# 2560_breakout.net
KiCad netlist of a schematic drawn in EAGLE
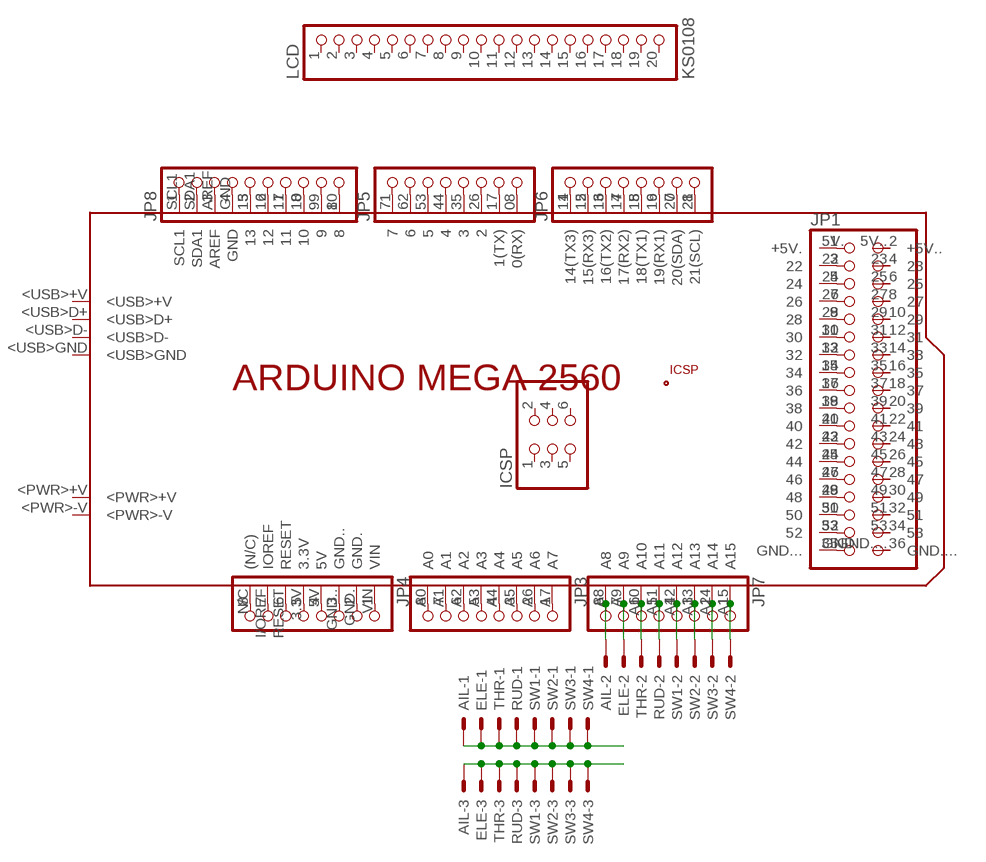
[diagram p0: schematic, sheet 1]

(export (version "E")
  (design (tool "Eeschema 10.0.6"))
  (components
    (comp (ref "AIL")
      (value "JST-XH-03-PIN-LONG-PAD")
      (footprint "eagle-import:JST-XH-03-PACKAGE-LONG-PAD")
      (libsource (lib "eagle-import") (part "JST-XH-03-PIN-LONG-PAD"))
    )
    (comp (ref "ELE")
      (value "JST-XH-03-PIN-LONG-PAD")
      (footprint "eagle-import:JST-XH-03-PACKAGE-LONG-PAD")
      (libsource (lib "eagle-import") (part "JST-XH-03-PIN-LONG-PAD"))
    )
    (comp (ref "ICSP")
      (value "PINHD-2X3")
      (footprint "eagle-import:2X03")
      (libsource (lib "eagle-import") (part "PINHD-2X3"))
    )
    (comp (ref "JP1")
      (value "PINHD-2X18")
      (footprint "eagle-import:2X18")
      (libsource (lib "eagle-import") (part "PINHD-2X18"))
    )
    (comp (ref "JP3")
      (value "PINHD-1X8")
      (footprint "eagle-import:1X08")
      (libsource (lib "eagle-import") (part "PINHD-1X8"))
    )
    (comp (ref "JP4")
      (value "PINHD-1X8")
      (footprint "eagle-import:1X08")
      (libsource (lib "eagle-import") (part "PINHD-1X8"))
    )
    (comp (ref "JP5")
      (value "PINHD-1X8")
      (footprint "eagle-import:1X08")
      (libsource (lib "eagle-import") (part "PINHD-1X8"))
    )
    (comp (ref "JP6")
      (value "PINHD-1X8")
      (footprint "eagle-import:1X08")
      (libsource (lib "eagle-import") (part "PINHD-1X8"))
    )
    (comp (ref "JP7")
      (value "PINHD-1X8")
      (footprint "eagle-import:1X08")
      (libsource (lib "eagle-import") (part "PINHD-1X8"))
    )
    (comp (ref "JP8")
      (value "PINHD-1X10")
      (footprint "eagle-import:1X10")
      (libsource (lib "eagle-import") (part "PINHD-1X10"))
    )
    (comp (ref "LCD")
      (value "KS0108")
      (footprint "eagle-import:1X20")
      (libsource (lib "eagle-import") (part "PINHD-1X20"))
    )
    (comp (ref "PCB1")
      (value "ARDUINO_MEGA2560")
      (footprint "eagle-import:ARDUINO_MEGA2560")
      (libsource (lib "eagle-import") (part "ARDUINO_MEGA2560"))
    )
    (comp (ref "RUD")
      (value "JST-XH-03-PIN-LONG-PAD")
      (footprint "eagle-import:JST-XH-03-PACKAGE-LONG-PAD")
      (libsource (lib "eagle-import") (part "JST-XH-03-PIN-LONG-PAD"))
    )
    (comp (ref "SW1")
      (value "JST-XH-03-PIN-LONG-PAD")
      (footprint "eagle-import:JST-XH-03-PACKAGE-LONG-PAD")
      (libsource (lib "eagle-import") (part "JST-XH-03-PIN-LONG-PAD"))
    )
    (comp (ref "SW2")
      (value "JST-XH-03-PIN-LONG-PAD")
      (footprint "eagle-import:JST-XH-03-PACKAGE-LONG-PAD")
      (libsource (lib "eagle-import") (part "JST-XH-03-PIN-LONG-PAD"))
    )
    (comp (ref "SW3")
      (value "JST-XH-03-PIN-LONG-PAD")
      (footprint "eagle-import:JST-XH-03-PACKAGE-LONG-PAD")
      (libsource (lib "eagle-import") (part "JST-XH-03-PIN-LONG-PAD"))
    )
    (comp (ref "SW4")
      (value "JST-XH-03-PIN-LONG-PAD")
      (footprint "eagle-import:JST-XH-03-PACKAGE-LONG-PAD")
      (libsource (lib "eagle-import") (part "JST-XH-03-PIN-LONG-PAD"))
    )
    (comp (ref "THR")
      (value "JST-XH-03-PIN-LONG-PAD")
      (footprint "eagle-import:JST-XH-03-PACKAGE-LONG-PAD")
      (libsource (lib "eagle-import") (part "JST-XH-03-PIN-LONG-PAD"))
    )
  )
  (nets
    (net (code "1") (name "Net-(AILA-S)") (class "Default")
      (node (ref "AIL") (pin "1") (pinfunction "S_1") (pintype "passive"))
      (node (ref "ELE") (pin "1") (pinfunction "S_1") (pintype "passive"))
      (node (ref "RUD") (pin "1") (pinfunction "S_1") (pintype "passive"))
      (node (ref "SW1") (pin "1") (pinfunction "S_1") (pintype "passive"))
      (node (ref "SW2") (pin "1") (pinfunction "S_1") (pintype "passive"))
      (node (ref "SW3") (pin "1") (pinfunction "S_1") (pintype "passive"))
      (node (ref "SW4") (pin "1") (pinfunction "S_1") (pintype "passive"))
      (node (ref "THR") (pin "1") (pinfunction "S_1") (pintype "passive"))
    )
    (net (code "2") (name "Net-(AILB-S)") (class "Default")
      (node (ref "AIL") (pin "2") (pinfunction "S_2") (pintype "passive"))
      (node (ref "JP7") (pin "8") (pinfunction "8_8") (pintype "passive"))
      (node (ref "PCB1") (pin "A8") (pinfunction "A8_A8") (pintype "bidirectional"))
    )
    (net (code "3") (name "Net-(AILC-S)") (class "Default")
      (node (ref "AIL") (pin "3") (pinfunction "S_3") (pintype "passive"))
      (node (ref "ELE") (pin "3") (pinfunction "S_3") (pintype "passive"))
      (node (ref "RUD") (pin "3") (pinfunction "S_3") (pintype "passive"))
      (node (ref "SW1") (pin "3") (pinfunction "S_3") (pintype "passive"))
      (node (ref "SW2") (pin "3") (pinfunction "S_3") (pintype "passive"))
      (node (ref "SW3") (pin "3") (pinfunction "S_3") (pintype "passive"))
      (node (ref "SW4") (pin "3") (pinfunction "S_3") (pintype "passive"))
      (node (ref "THR") (pin "3") (pinfunction "S_3") (pintype "passive"))
    )
    (net (code "4") (name "Net-(ELEB-S)") (class "Default")
      (node (ref "ELE") (pin "2") (pinfunction "S_2") (pintype "passive"))
      (node (ref "JP7") (pin "7") (pinfunction "7_7") (pintype "passive"))
      (node (ref "PCB1") (pin "A9") (pinfunction "A9_A9") (pintype "bidirectional"))
    )
    (net (code "5") (name "Net-(JP1-Pad3)") (class "Default")
      (node (ref "JP1") (pin "3") (pinfunction "3_3") (pintype "passive"))
      (node (ref "PCB1") (pin "22") (pinfunction "22_22") (pintype "bidirectional"))
    )
    (net (code "6") (name "Net-(JP1-Pad5)") (class "Default")
      (node (ref "JP1") (pin "5") (pinfunction "5_5") (pintype "passive"))
      (node (ref "PCB1") (pin "24") (pinfunction "24_24") (pintype "bidirectional"))
    )
    (net (code "7") (name "Net-(JP1-Pad7)") (class "Default")
      (node (ref "JP1") (pin "7") (pinfunction "7_7") (pintype "passive"))
      (node (ref "PCB1") (pin "26") (pinfunction "26_26") (pintype "bidirectional"))
    )
    (net (code "8") (name "Net-(JP1-Pad9)") (class "Default")
      (node (ref "JP1") (pin "9") (pinfunction "9_9") (pintype "passive"))
      (node (ref "PCB1") (pin "28") (pinfunction "28_28") (pintype "bidirectional"))
    )
    (net (code "9") (name "Net-(JP1-Pad11)") (class "Default")
      (node (ref "JP1") (pin "11") (pinfunction "11_11") (pintype "passive"))
      (node (ref "PCB1") (pin "30") (pinfunction "30_30") (pintype "bidirectional"))
    )
    (net (code "10") (name "Net-(JP1-Pad13)") (class "Default")
      (node (ref "JP1") (pin "13") (pinfunction "13_13") (pintype "passive"))
      (node (ref "PCB1") (pin "32") (pinfunction "32_32") (pintype "bidirectional"))
    )
    (net (code "11") (name "Net-(JP1-Pad15)") (class "Default")
      (node (ref "JP1") (pin "15") (pinfunction "15_15") (pintype "passive"))
      (node (ref "PCB1") (pin "34") (pinfunction "34_34") (pintype "bidirectional"))
    )
    (net (code "12") (name "Net-(JP1-Pad17)") (class "Default")
      (node (ref "JP1") (pin "17") (pinfunction "17_17") (pintype "passive"))
      (node (ref "PCB1") (pin "36") (pinfunction "36_36") (pintype "bidirectional"))
    )
    (net (code "13") (name "Net-(JP1-Pad19)") (class "Default")
      (node (ref "JP1") (pin "19") (pinfunction "19_19") (pintype "passive"))
      (node (ref "PCB1") (pin "38") (pinfunction "38_38") (pintype "bidirectional"))
    )
    (net (code "14") (name "Net-(JP1-Pad21)") (class "Default")
      (node (ref "JP1") (pin "21") (pinfunction "21_21") (pintype "passive"))
      (node (ref "PCB1") (pin "40") (pinfunction "40_40") (pintype "bidirectional"))
    )
    (net (code "15") (name "Net-(JP1-Pad23)") (class "Default")
      (node (ref "JP1") (pin "23") (pinfunction "23_23") (pintype "passive"))
      (node (ref "PCB1") (pin "42") (pinfunction "42_42") (pintype "bidirectional"))
    )
    (net (code "16") (name "Net-(JP1-Pad25)") (class "Default")
      (node (ref "JP1") (pin "25") (pinfunction "25_25") (pintype "passive"))
      (node (ref "PCB1") (pin "44") (pinfunction "44_44") (pintype "bidirectional"))
    )
    (net (code "17") (name "Net-(JP1-Pad27)") (class "Default")
      (node (ref "JP1") (pin "27") (pinfunction "27_27") (pintype "passive"))
      (node (ref "PCB1") (pin "46") (pinfunction "46_46") (pintype "bidirectional"))
    )
    (net (code "18") (name "Net-(JP1-Pad29)") (class "Default")
      (node (ref "JP1") (pin "29") (pinfunction "29_29") (pintype "passive"))
      (node (ref "PCB1") (pin "48") (pinfunction "48_48") (pintype "bidirectional"))
    )
    (net (code "19") (name "Net-(JP1-Pad31)") (class "Default")
      (node (ref "JP1") (pin "31") (pinfunction "31_31") (pintype "passive"))
      (node (ref "PCB1") (pin "50") (pinfunction "50_50") (pintype "bidirectional"))
    )
    (net (code "20") (name "Net-(JP1-Pad33)") (class "Default")
      (node (ref "JP1") (pin "33") (pinfunction "33_33") (pintype "passive"))
      (node (ref "PCB1") (pin "52") (pinfunction "52_52") (pintype "bidirectional"))
    )
    (net (code "21") (name "Net-(JP1-Pad35)") (class "Default")
      (node (ref "JP1") (pin "35") (pinfunction "35_35") (pintype "passive"))
      (node (ref "PCB1") (pin "GND...") (pinfunction "GND..._GND...") (pintype "bidirectional"))
    )
    (net (code "22") (name "Net-(JP3-Pad1)") (class "Default")
      (node (ref "JP3") (pin "1") (pinfunction "1_1") (pintype "passive"))
      (node (ref "PCB1") (pin "A7") (pinfunction "A7_A7") (pintype "bidirectional"))
    )
    (net (code "23") (name "Net-(JP3-Pad2)") (class "Default")
      (node (ref "JP3") (pin "2") (pinfunction "2_2") (pintype "passive"))
      (node (ref "PCB1") (pin "A6") (pinfunction "A6_A6") (pintype "bidirectional"))
    )
    (net (code "24") (name "Net-(JP3-Pad3)") (class "Default")
      (node (ref "JP3") (pin "3") (pinfunction "3_3") (pintype "passive"))
      (node (ref "PCB1") (pin "A5") (pinfunction "A5_A5") (pintype "bidirectional"))
    )
    (net (code "25") (name "Net-(JP3-Pad4)") (class "Default")
      (node (ref "JP3") (pin "4") (pinfunction "4_4") (pintype "passive"))
      (node (ref "PCB1") (pin "A4") (pinfunction "A4_A4") (pintype "bidirectional"))
    )
    (net (code "26") (name "Net-(JP3-Pad5)") (class "Default")
      (node (ref "JP3") (pin "5") (pinfunction "5_5") (pintype "passive"))
      (node (ref "PCB1") (pin "A3") (pinfunction "A3_A3") (pintype "bidirectional"))
    )
    (net (code "27") (name "Net-(JP3-Pad6)") (class "Default")
      (node (ref "JP3") (pin "6") (pinfunction "6_6") (pintype "passive"))
      (node (ref "PCB1") (pin "A2") (pinfunction "A2_A2") (pintype "bidirectional"))
    )
    (net (code "28") (name "Net-(JP3-Pad7)") (class "Default")
      (node (ref "JP3") (pin "7") (pinfunction "7_7") (pintype "passive"))
      (node (ref "PCB1") (pin "A1") (pinfunction "A1_A1") (pintype "bidirectional"))
    )
    (net (code "29") (name "Net-(JP3-Pad8)") (class "Default")
      (node (ref "JP3") (pin "8") (pinfunction "8_8") (pintype "passive"))
      (node (ref "PCB1") (pin "A0") (pinfunction "A0_A0") (pintype "bidirectional"))
    )
    (net (code "30") (name "Net-(JP4-Pad1)") (class "Default")
      (node (ref "JP4") (pin "1") (pinfunction "1_1") (pintype "passive"))
      (node (ref "PCB1") (pin "VIN") (pinfunction "VIN_VIN") (pintype "bidirectional"))
    )
    (net (code "31") (name "Net-(JP4-Pad2)") (class "Default")
      (node (ref "JP4") (pin "2") (pinfunction "2_2") (pintype "passive"))
      (node (ref "PCB1") (pin "GND.") (pinfunction "GND._GND.") (pintype "bidirectional"))
    )
    (net (code "32") (name "Net-(JP4-Pad3)") (class "Default")
      (node (ref "JP4") (pin "3") (pinfunction "3_3") (pintype "passive"))
      (node (ref "PCB1") (pin "GND..") (pinfunction "GND.._GND..") (pintype "bidirectional"))
    )
    (net (code "33") (name "Net-(JP4-Pad4)") (class "Default")
      (node (ref "JP4") (pin "4") (pinfunction "4_4") (pintype "passive"))
      (node (ref "PCB1") (pin "5V") (pinfunction "5V_5V") (pintype "bidirectional"))
    )
    (net (code "34") (name "Net-(JP4-Pad5)") (class "Default")
      (node (ref "JP4") (pin "5") (pinfunction "5_5") (pintype "passive"))
      (node (ref "PCB1") (pin "3.3V") (pinfunction "3.3V_3.3V") (pintype "bidirectional"))
    )
    (net (code "35") (name "Net-(JP4-Pad6)") (class "Default")
      (node (ref "JP4") (pin "6") (pinfunction "6_6") (pintype "passive"))
      (node (ref "PCB1") (pin "RESET") (pinfunction "RESET_RESET") (pintype "bidirectional"))
    )
    (net (code "36") (name "Net-(JP5-Pad1)") (class "Default")
      (node (ref "JP5") (pin "1") (pinfunction "1_1") (pintype "passive"))
      (node (ref "PCB1") (pin "7") (pinfunction "7_7") (pintype "bidirectional"))
    )
    (net (code "37") (name "Net-(JP5-Pad2)") (class "Default")
      (node (ref "JP5") (pin "2") (pinfunction "2_2") (pintype "passive"))
      (node (ref "PCB1") (pin "6") (pinfunction "6_6") (pintype "bidirectional"))
    )
    (net (code "38") (name "Net-(JP5-Pad3)") (class "Default")
      (node (ref "JP5") (pin "3") (pinfunction "3_3") (pintype "passive"))
      (node (ref "PCB1") (pin "5") (pinfunction "5_5") (pintype "bidirectional"))
    )
    (net (code "39") (name "Net-(JP5-Pad4)") (class "Default")
      (node (ref "JP5") (pin "4") (pinfunction "4_4") (pintype "passive"))
      (node (ref "PCB1") (pin "4") (pinfunction "4_4") (pintype "bidirectional"))
    )
    (net (code "40") (name "Net-(JP5-Pad5)") (class "Default")
      (node (ref "JP5") (pin "5") (pinfunction "5_5") (pintype "passive"))
      (node (ref "PCB1") (pin "3") (pinfunction "3_3") (pintype "bidirectional"))
    )
    (net (code "41") (name "Net-(JP5-Pad6)") (class "Default")
      (node (ref "JP5") (pin "6") (pinfunction "6_6") (pintype "passive"))
      (node (ref "PCB1") (pin "2") (pinfunction "2_2") (pintype "bidirectional"))
    )
    (net (code "42") (name "Net-(JP8-Pad1)") (class "Default")
      (node (ref "JP8") (pin "1") (pinfunction "1_1") (pintype "passive"))
      (node (ref "PCB1") (pin "SCL1") (pinfunction "SCL1_SCL1") (pintype "bidirectional"))
    )
    (net (code "43") (name "Net-(JP8-Pad2)") (class "Default")
      (node (ref "JP8") (pin "2") (pinfunction "2_2") (pintype "passive"))
      (node (ref "PCB1") (pin "SDA1") (pinfunction "SDA1_SDA1") (pintype "bidirectional"))
    )
    (net (code "44") (name "Net-(JP8-Pad3)") (class "Default")
      (node (ref "JP8") (pin "3") (pinfunction "3_3") (pintype "passive"))
      (node (ref "PCB1") (pin "AREF") (pinfunction "AREF_AREF") (pintype "bidirectional"))
    )
    (net (code "45") (name "Net-(JP8-Pad4)") (class "Default")
      (node (ref "JP8") (pin "4") (pinfunction "4_4") (pintype "passive"))
      (node (ref "PCB1") (pin "GND") (pinfunction "GND_GND") (pintype "bidirectional"))
    )
    (net (code "46") (name "Net-(JP8-Pad5)") (class "Default")
      (node (ref "JP8") (pin "5") (pinfunction "5_5") (pintype "passive"))
      (node (ref "PCB1") (pin "13") (pinfunction "13_13") (pintype "bidirectional"))
    )
    (net (code "47") (name "Net-(JP8-Pad6)") (class "Default")
      (node (ref "JP8") (pin "6") (pinfunction "6_6") (pintype "passive"))
      (node (ref "PCB1") (pin "12") (pinfunction "12_12") (pintype "bidirectional"))
    )
    (net (code "48") (name "Net-(JP8-Pad7)") (class "Default")
      (node (ref "JP8") (pin "7") (pinfunction "7_7") (pintype "passive"))
      (node (ref "PCB1") (pin "11") (pinfunction "11_11") (pintype "bidirectional"))
    )
    (net (code "49") (name "Net-(JP8-Pad8)") (class "Default")
      (node (ref "JP8") (pin "8") (pinfunction "8_8") (pintype "passive"))
      (node (ref "PCB1") (pin "10") (pinfunction "10_10") (pintype "bidirectional"))
    )
    (net (code "50") (name "Net-(JP8-Pad9)") (class "Default")
      (node (ref "JP8") (pin "9") (pinfunction "9_9") (pintype "passive"))
      (node (ref "PCB1") (pin "9") (pinfunction "9_9") (pintype "bidirectional"))
    )
    (net (code "51") (name "Net-(JP8-Pad10)") (class "Default")
      (node (ref "JP8") (pin "10") (pinfunction "10_10") (pintype "passive"))
      (node (ref "PCB1") (pin "8") (pinfunction "8_8") (pintype "bidirectional"))
    )
    (net (code "52") (name "Net-(PCB1-(N{slash}C))") (class "Default")
      (node (ref "JP4") (pin "8") (pinfunction "8_8") (pintype "passive"))
      (node (ref "PCB1") (pin "N/C") (pinfunction "(N/C)_N/C") (pintype "bidirectional"))
    )
    (net (code "53") (name "Net-(PCB1-+5V.)") (class "Default")
      (node (ref "JP1") (pin "1") (pinfunction "1_1") (pintype "passive"))
      (node (ref "PCB1") (pin "5V.") (pinfunction "+5V._5V.") (pintype "bidirectional"))
    )
    (net (code "54") (name "Net-(PCB1-0(RX))") (class "Default")
      (node (ref "JP5") (pin "8") (pinfunction "8_8") (pintype "passive"))
      (node (ref "PCB1") (pin "0") (pinfunction "0(RX)_0") (pintype "bidirectional"))
    )
    (net (code "55") (name "Net-(PCB1-1(TX))") (class "Default")
      (node (ref "JP5") (pin "7") (pinfunction "7_7") (pintype "passive"))
      (node (ref "PCB1") (pin "1") (pinfunction "1(TX)_1") (pintype "bidirectional"))
    )
    (net (code "56") (name "Net-(PCB1-14(TX3))") (class "Default")
      (node (ref "JP6") (pin "1") (pinfunction "1_1") (pintype "passive"))
      (node (ref "PCB1") (pin "14") (pinfunction "14(TX3)_14") (pintype "bidirectional"))
    )
    (net (code "57") (name "Net-(PCB1-15(RX3))") (class "Default")
      (node (ref "JP6") (pin "2") (pinfunction "2_2") (pintype "passive"))
      (node (ref "PCB1") (pin "15") (pinfunction "15(RX3)_15") (pintype "bidirectional"))
    )
    (net (code "58") (name "Net-(PCB1-16(TX2))") (class "Default")
      (node (ref "JP6") (pin "3") (pinfunction "3_3") (pintype "passive"))
      (node (ref "PCB1") (pin "16") (pinfunction "16(TX2)_16") (pintype "bidirectional"))
    )
    (net (code "59") (name "Net-(PCB1-17(RX2))") (class "Default")
      (node (ref "JP6") (pin "4") (pinfunction "4_4") (pintype "passive"))
      (node (ref "PCB1") (pin "17") (pinfunction "17(RX2)_17") (pintype "bidirectional"))
    )
    (net (code "60") (name "Net-(PCB1-18(TX1))") (class "Default")
      (node (ref "JP6") (pin "5") (pinfunction "5_5") (pintype "passive"))
      (node (ref "PCB1") (pin "18") (pinfunction "18(TX1)_18") (pintype "bidirectional"))
    )
    (net (code "61") (name "Net-(PCB1-19(RX1))") (class "Default")
      (node (ref "JP6") (pin "6") (pinfunction "6_6") (pintype "passive"))
      (node (ref "PCB1") (pin "19") (pinfunction "19(RX1)_19") (pintype "bidirectional"))
    )
    (net (code "62") (name "Net-(PCB1-20(SDA))") (class "Default")
      (node (ref "JP6") (pin "7") (pinfunction "7_7") (pintype "passive"))
      (node (ref "PCB1") (pin "20") (pinfunction "20(SDA)_20") (pintype "bidirectional"))
    )
    (net (code "63") (name "Net-(PCB1-21(SCL))") (class "Default")
      (node (ref "JP6") (pin "8") (pinfunction "8_8") (pintype "passive"))
      (node (ref "PCB1") (pin "21") (pinfunction "21(SCL)_21") (pintype "bidirectional"))
    )
    (net (code "64") (name "Net-(PCB1-IOREF)") (class "Default")
      (node (ref "JP4") (pin "7") (pinfunction "7_7") (pintype "passive"))
      (node (ref "PCB1") (pin "I/OREF") (pinfunction "IOREF_I/OREF") (pintype "bidirectional"))
    )
    (net (code "65") (name "Net-(RUDB-S)") (class "Default")
      (node (ref "JP7") (pin "5") (pinfunction "5_5") (pintype "passive"))
      (node (ref "PCB1") (pin "A11") (pinfunction "A11_A11") (pintype "bidirectional"))
      (node (ref "RUD") (pin "2") (pinfunction "S_2") (pintype "passive"))
    )
    (net (code "66") (name "Net-(SW1B-S)") (class "Default")
      (node (ref "JP7") (pin "4") (pinfunction "4_4") (pintype "passive"))
      (node (ref "PCB1") (pin "A12") (pinfunction "A12_A12") (pintype "bidirectional"))
      (node (ref "SW1") (pin "2") (pinfunction "S_2") (pintype "passive"))
    )
    (net (code "67") (name "Net-(SW2B-S)") (class "Default")
      (node (ref "JP7") (pin "3") (pinfunction "3_3") (pintype "passive"))
      (node (ref "PCB1") (pin "A13") (pinfunction "A13_A13") (pintype "bidirectional"))
      (node (ref "SW2") (pin "2") (pinfunction "S_2") (pintype "passive"))
    )
    (net (code "68") (name "Net-(SW3B-S)") (class "Default")
      (node (ref "JP7") (pin "2") (pinfunction "2_2") (pintype "passive"))
      (node (ref "PCB1") (pin "A14") (pinfunction "A14_A14") (pintype "bidirectional"))
      (node (ref "SW3") (pin "2") (pinfunction "S_2") (pintype "passive"))
    )
    (net (code "69") (name "Net-(SW4B-S)") (class "Default")
      (node (ref "JP7") (pin "1") (pinfunction "1_1") (pintype "passive"))
      (node (ref "PCB1") (pin "A15") (pinfunction "A15_A15") (pintype "bidirectional"))
      (node (ref "SW4") (pin "2") (pinfunction "S_2") (pintype "passive"))
    )
    (net (code "70") (name "Net-(THRB-S)") (class "Default")
      (node (ref "JP7") (pin "6") (pinfunction "6_6") (pintype "passive"))
      (node (ref "PCB1") (pin "A10") (pinfunction "A10_A10") (pintype "bidirectional"))
      (node (ref "THR") (pin "2") (pinfunction "S_2") (pintype "passive"))
    )
    (net (code "71") (name "unconnected-(ICSP-Pad1)") (class "Default")
      (node (ref "ICSP") (pin "1") (pinfunction "1_1") (pintype "passive"))
    )
    (net (code "72") (name "unconnected-(ICSP-Pad2)") (class "Default")
      (node (ref "ICSP") (pin "2") (pinfunction "2_2") (pintype "passive"))
    )
    (net (code "73") (name "unconnected-(ICSP-Pad3)") (class "Default")
      (node (ref "ICSP") (pin "3") (pinfunction "3_3") (pintype "passive"))
    )
    (net (code "74") (name "unconnected-(ICSP-Pad4)") (class "Default")
      (node (ref "ICSP") (pin "4") (pinfunction "4_4") (pintype "passive"))
    )
    (net (code "75") (name "unconnected-(ICSP-Pad5)") (class "Default")
      (node (ref "ICSP") (pin "5") (pinfunction "5_5") (pintype "passive"))
    )
    (net (code "76") (name "unconnected-(ICSP-Pad6)") (class "Default")
      (node (ref "ICSP") (pin "6") (pinfunction "6_6") (pintype "passive"))
    )
    (net (code "77") (name "unconnected-(JP1-Pad2)") (class "Default")
      (node (ref "JP1") (pin "2") (pinfunction "2_2") (pintype "passive"))
    )
    (net (code "78") (name "unconnected-(JP1-Pad4)") (class "Default")
      (node (ref "JP1") (pin "4") (pinfunction "4_4") (pintype "passive"))
    )
    (net (code "79") (name "unconnected-(JP1-Pad6)") (class "Default")
      (node (ref "JP1") (pin "6") (pinfunction "6_6") (pintype "passive"))
    )
    (net (code "80") (name "unconnected-(JP1-Pad8)") (class "Default")
      (node (ref "JP1") (pin "8") (pinfunction "8_8") (pintype "passive"))
    )
    (net (code "81") (name "unconnected-(JP1-Pad10)") (class "Default")
      (node (ref "JP1") (pin "10") (pinfunction "10_10") (pintype "passive"))
    )
    (net (code "82") (name "unconnected-(JP1-Pad12)") (class "Default")
      (node (ref "JP1") (pin "12") (pinfunction "12_12") (pintype "passive"))
    )
    (net (code "83") (name "unconnected-(JP1-Pad14)") (class "Default")
      (node (ref "JP1") (pin "14") (pinfunction "14_14") (pintype "passive"))
    )
    (net (code "84") (name "unconnected-(JP1-Pad16)") (class "Default")
      (node (ref "JP1") (pin "16") (pinfunction "16_16") (pintype "passive"))
    )
    (net (code "85") (name "unconnected-(JP1-Pad18)") (class "Default")
      (node (ref "JP1") (pin "18") (pinfunction "18_18") (pintype "passive"))
    )
    (net (code "86") (name "unconnected-(JP1-Pad20)") (class "Default")
      (node (ref "JP1") (pin "20") (pinfunction "20_20") (pintype "passive"))
    )
    (net (code "87") (name "unconnected-(JP1-Pad22)") (class "Default")
      (node (ref "JP1") (pin "22") (pinfunction "22_22") (pintype "passive"))
    )
    (net (code "88") (name "unconnected-(JP1-Pad24)") (class "Default")
      (node (ref "JP1") (pin "24") (pinfunction "24_24") (pintype "passive"))
    )
    (net (code "89") (name "unconnected-(JP1-Pad26)") (class "Default")
      (node (ref "JP1") (pin "26") (pinfunction "26_26") (pintype "passive"))
    )
    (net (code "90") (name "unconnected-(JP1-Pad28)") (class "Default")
      (node (ref "JP1") (pin "28") (pinfunction "28_28") (pintype "passive"))
    )
    (net (code "91") (name "unconnected-(JP1-Pad30)") (class "Default")
      (node (ref "JP1") (pin "30") (pinfunction "30_30") (pintype "passive"))
    )
    (net (code "92") (name "unconnected-(JP1-Pad32)") (class "Default")
      (node (ref "JP1") (pin "32") (pinfunction "32_32") (pintype "passive"))
    )
    (net (code "93") (name "unconnected-(JP1-Pad34)") (class "Default")
      (node (ref "JP1") (pin "34") (pinfunction "34_34") (pintype "passive"))
    )
    (net (code "94") (name "unconnected-(JP1-Pad36)") (class "Default")
      (node (ref "JP1") (pin "36") (pinfunction "36_36") (pintype "passive"))
    )
    (net (code "95") (name "unconnected-(LCD-Pad1)") (class "Default")
      (node (ref "LCD") (pin "1") (pinfunction "1_1") (pintype "passive"))
    )
    (net (code "96") (name "unconnected-(LCD-Pad2)") (class "Default")
      (node (ref "LCD") (pin "2") (pinfunction "2_2") (pintype "passive"))
    )
    (net (code "97") (name "unconnected-(LCD-Pad3)") (class "Default")
      (node (ref "LCD") (pin "3") (pinfunction "3_3") (pintype "passive"))
    )
    (net (code "98") (name "unconnected-(LCD-Pad4)") (class "Default")
      (node (ref "LCD") (pin "4") (pinfunction "4_4") (pintype "passive"))
    )
    (net (code "99") (name "unconnected-(LCD-Pad5)") (class "Default")
      (node (ref "LCD") (pin "5") (pinfunction "5_5") (pintype "passive"))
    )
    (net (code "100") (name "unconnected-(LCD-Pad6)") (class "Default")
      (node (ref "LCD") (pin "6") (pinfunction "6_6") (pintype "passive"))
    )
    (net (code "101") (name "unconnected-(LCD-Pad7)") (class "Default")
      (node (ref "LCD") (pin "7") (pinfunction "7_7") (pintype "passive"))
    )
    (net (code "102") (name "unconnected-(LCD-Pad8)") (class "Default")
      (node (ref "LCD") (pin "8") (pinfunction "8_8") (pintype "passive"))
    )
    (net (code "103") (name "unconnected-(LCD-Pad9)") (class "Default")
      (node (ref "LCD") (pin "9") (pinfunction "9_9") (pintype "passive"))
    )
    (net (code "104") (name "unconnected-(LCD-Pad10)") (class "Default")
      (node (ref "LCD") (pin "10") (pinfunction "10_10") (pintype "passive"))
    )
    (net (code "105") (name "unconnected-(LCD-Pad11)") (class "Default")
      (node (ref "LCD") (pin "11") (pinfunction "11_11") (pintype "passive"))
    )
    (net (code "106") (name "unconnected-(LCD-Pad12)") (class "Default")
      (node (ref "LCD") (pin "12") (pinfunction "12_12") (pintype "passive"))
    )
    (net (code "107") (name "unconnected-(LCD-Pad13)") (class "Default")
      (node (ref "LCD") (pin "13") (pinfunction "13_13") (pintype "passive"))
    )
    (net (code "108") (name "unconnected-(LCD-Pad14)") (class "Default")
      (node (ref "LCD") (pin "14") (pinfunction "14_14") (pintype "passive"))
    )
    (net (code "109") (name "unconnected-(LCD-Pad15)") (class "Default")
      (node (ref "LCD") (pin "15") (pinfunction "15_15") (pintype "passive"))
    )
    (net (code "110") (name "unconnected-(LCD-Pad16)") (class "Default")
      (node (ref "LCD") (pin "16") (pinfunction "16_16") (pintype "passive"))
    )
    (net (code "111") (name "unconnected-(LCD-Pad17)") (class "Default")
      (node (ref "LCD") (pin "17") (pinfunction "17_17") (pintype "passive"))
    )
    (net (code "112") (name "unconnected-(LCD-Pad18)") (class "Default")
      (node (ref "LCD") (pin "18") (pinfunction "18_18") (pintype "passive"))
    )
    (net (code "113") (name "unconnected-(LCD-Pad19)") (class "Default")
      (node (ref "LCD") (pin "19") (pinfunction "19_19") (pintype "passive"))
    )
    (net (code "114") (name "unconnected-(LCD-Pad20)") (class "Default")
      (node (ref "LCD") (pin "20") (pinfunction "20_20") (pintype "passive"))
    )
    (net (code "115") (name "unconnected-(PCB1-+5V..-Pad5V..)") (class "Default")
      (node (ref "PCB1") (pin "5V..") (pinfunction "+5V.._5V..") (pintype "bidirectional"))
    )
    (net (code "116") (name "unconnected-(PCB1-Pad+5V_)") (class "Default")
      (node (ref "PCB1") (pin "+5V_") (pinfunction "+5V__+5V_") (pintype "bidirectional"))
    )
    (net (code "117") (name "unconnected-(PCB1-Pad23)") (class "Default")
      (node (ref "PCB1") (pin "23") (pinfunction "23_23") (pintype "bidirectional"))
    )
    (net (code "118") (name "unconnected-(PCB1-Pad25)") (class "Default")
      (node (ref "PCB1") (pin "25") (pinfunction "25_25") (pintype "bidirectional"))
    )
    (net (code "119") (name "unconnected-(PCB1-Pad27)") (class "Default")
      (node (ref "PCB1") (pin "27") (pinfunction "27_27") (pintype "bidirectional"))
    )
    (net (code "120") (name "unconnected-(PCB1-Pad29)") (class "Default")
      (node (ref "PCB1") (pin "29") (pinfunction "29_29") (pintype "bidirectional"))
    )
    (net (code "121") (name "unconnected-(PCB1-Pad31)") (class "Default")
      (node (ref "PCB1") (pin "31") (pinfunction "31_31") (pintype "bidirectional"))
    )
    (net (code "122") (name "unconnected-(PCB1-Pad33)") (class "Default")
      (node (ref "PCB1") (pin "33") (pinfunction "33_33") (pintype "bidirectional"))
    )
    (net (code "123") (name "unconnected-(PCB1-Pad35)") (class "Default")
      (node (ref "PCB1") (pin "35") (pinfunction "35_35") (pintype "bidirectional"))
    )
    (net (code "124") (name "unconnected-(PCB1-Pad37)") (class "Default")
      (node (ref "PCB1") (pin "37") (pinfunction "37_37") (pintype "bidirectional"))
    )
    (net (code "125") (name "unconnected-(PCB1-Pad39)") (class "Default")
      (node (ref "PCB1") (pin "39") (pinfunction "39_39") (pintype "bidirectional"))
    )
    (net (code "126") (name "unconnected-(PCB1-Pad41)") (class "Default")
      (node (ref "PCB1") (pin "41") (pinfunction "41_41") (pintype "bidirectional"))
    )
    (net (code "127") (name "unconnected-(PCB1-Pad43)") (class "Default")
      (node (ref "PCB1") (pin "43") (pinfunction "43_43") (pintype "bidirectional"))
    )
    (net (code "128") (name "unconnected-(PCB1-Pad45)") (class "Default")
      (node (ref "PCB1") (pin "45") (pinfunction "45_45") (pintype "bidirectional"))
    )
    (net (code "129") (name "unconnected-(PCB1-Pad47)") (class "Default")
      (node (ref "PCB1") (pin "47") (pinfunction "47_47") (pintype "bidirectional"))
    )
    (net (code "130") (name "unconnected-(PCB1-Pad49)") (class "Default")
      (node (ref "PCB1") (pin "49") (pinfunction "49_49") (pintype "bidirectional"))
    )
    (net (code "131") (name "unconnected-(PCB1-Pad51)") (class "Default")
      (node (ref "PCB1") (pin "51") (pinfunction "51_51") (pintype "bidirectional"))
    )
    (net (code "132") (name "unconnected-(PCB1-Pad53)") (class "Default")
      (node (ref "PCB1") (pin "53") (pinfunction "53_53") (pintype "bidirectional"))
    )
    (net (code "133") (name "unconnected-(PCB1-Pad<PWR>+V)") (class "Default")
      (node (ref "PCB1") (pin "<PWR>+V") (pinfunction "<PWR>+V_<PWR>+V") (pintype "no_connect"))
    )
    (net (code "134") (name "unconnected-(PCB1-Pad<PWR>-V)") (class "Default")
      (node (ref "PCB1") (pin "<PWR>-V") (pinfunction "<PWR>-V_<PWR>-V") (pintype "no_connect"))
    )
    (net (code "135") (name "unconnected-(PCB1-Pad<USB>+V)") (class "Default")
      (node (ref "PCB1") (pin "<USB>+V") (pinfunction "<USB>+V_<USB>+V") (pintype "no_connect"))
    )
    (net (code "136") (name "unconnected-(PCB1-Pad<USB>D+)") (class "Default")
      (node (ref "PCB1") (pin "<USB>D+") (pinfunction "<USB>D+_<USB>D+") (pintype "no_connect"))
    )
    (net (code "137") (name "unconnected-(PCB1-Pad<USB>D-)") (class "Default")
      (node (ref "PCB1") (pin "<USB>D-") (pinfunction "<USB>D-_<USB>D-") (pintype "no_connect"))
    )
    (net (code "138") (name "unconnected-(PCB1-Pad<USB>GND)") (class "Default")
      (node (ref "PCB1") (pin "<USB>GND") (pinfunction "<USB>GND_<USB>GND") (pintype "no_connect"))
    )
    (net (code "139") (name "unconnected-(PCB1-PadGND....)") (class "Default")
      (node (ref "PCB1") (pin "GND....") (pinfunction "GND...._GND....") (pintype "bidirectional"))
    )
    (net (code "140") (name "unconnected-(PCB1-PadGND__)") (class "Default")
      (node (ref "PCB1") (pin "GND__") (pinfunction "GND___GND__") (pintype "bidirectional"))
    )
    (net (code "141") (name "unconnected-(PCB1-PadMISO)") (class "Default")
      (node (ref "PCB1") (pin "MISO") (pinfunction "MISO_MISO") (pintype "bidirectional"))
    )
    (net (code "142") (name "unconnected-(PCB1-PadMOSI)") (class "Default")
      (node (ref "PCB1") (pin "MOSI") (pinfunction "MOSI_MOSI") (pintype "bidirectional"))
    )
    (net (code "143") (name "unconnected-(PCB1-PadRESET.)") (class "Default")
      (node (ref "PCB1") (pin "RESET.") (pinfunction "RESET._RESET.") (pintype "bidirectional"))
    )
    (net (code "144") (name "unconnected-(PCB1-PadSCK)") (class "Default")
      (node (ref "PCB1") (pin "SCK") (pinfunction "SCK_SCK") (pintype "bidirectional"))
    )
  )
)
